# ISPnub_v1_2.net
KiCad netlist of a schematic drawn in EAGLE
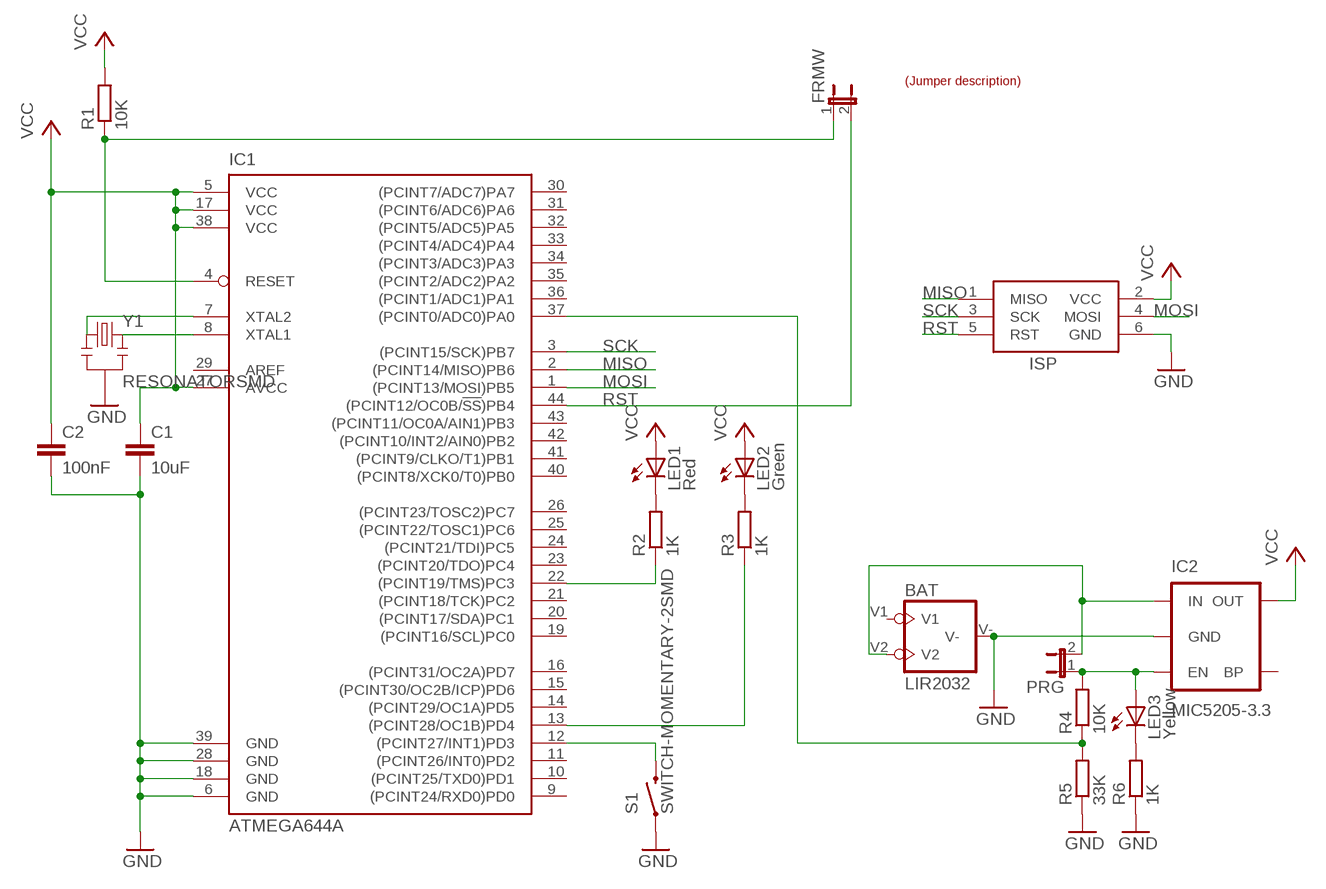
[diagram p0: schematic, sheet 1]

(export (version "E")
  (design (tool "Eeschema 10.0.6"))
  (components
    (comp (ref "BAT")
      (value "LIR2032")
      (footprint "eagle-import:BATT2032")
      (libsource (lib "eagle-import") (part "BATTERY_2032"))
    )
    (comp (ref "C1")
      (value "10uF")
      (footprint "eagle-import:C0805")
      (libsource (lib "eagle-import") (part "C-EUC0805"))
    )
    (comp (ref "C2")
      (value "100nF")
      (footprint "eagle-import:C0805")
      (libsource (lib "eagle-import") (part "C-EUC0805"))
    )
    (comp (ref "FRMW")
      (value "JP1E")
      (footprint "eagle-import:JP1")
      (libsource (lib "eagle-import") (part "JP1E"))
    )
    (comp (ref "IC1")
      (value "ATMEGA644A")
      (footprint "eagle-import:TQFP44")
      (fields (field (name "MPN") "ATMEGA644PV-10AU") (field (name "MPN_1") "ATMEGA1284PV-10AU"))
      (libsource (lib "eagle-import") (part "ATMEGA644A"))
    )
    (comp (ref "IC2")
      (value "MIC5205-3.3")
      (footprint "eagle-import:SOT23-5")
      (libsource (lib "eagle-import") (part "V_REG_LDOSMD"))
    )
    (comp (ref "ISP")
      (value "AVRISP-6")
      (footprint "eagle-import:AVRISP")
      (libsource (lib "eagle-import") (part "AVRISP-6"))
    )
    (comp (ref "LED1")
      (value "Red")
      (footprint "eagle-import:CHIP-LED0805")
      (libsource (lib "eagle-import") (part "LEDCHIP-LED0805"))
    )
    (comp (ref "LED2")
      (value "Green")
      (footprint "eagle-import:CHIP-LED0805")
      (libsource (lib "eagle-import") (part "LEDCHIP-LED0805"))
    )
    (comp (ref "LED3")
      (value "Yellow")
      (footprint "eagle-import:CHIP-LED0805")
      (libsource (lib "eagle-import") (part "LEDCHIP-LED0805"))
    )
    (comp (ref "PRG")
      (value "JP1E")
      (footprint "eagle-import:JP1")
      (libsource (lib "eagle-import") (part "JP1E"))
    )
    (comp (ref "R1")
      (value "10K")
      (footprint "eagle-import:R0805")
      (libsource (lib "eagle-import") (part "R-EU_R0805"))
    )
    (comp (ref "R2")
      (value "1K")
      (footprint "eagle-import:R0805")
      (libsource (lib "eagle-import") (part "R-EU_R0805"))
    )
    (comp (ref "R3")
      (value "1K")
      (footprint "eagle-import:R0805")
      (libsource (lib "eagle-import") (part "R-EU_R0805"))
    )
    (comp (ref "R4")
      (value "10K")
      (footprint "eagle-import:R0402")
      (libsource (lib "eagle-import") (part "R-EU_R0402"))
    )
    (comp (ref "R5")
      (value "33K")
      (footprint "eagle-import:R0402")
      (libsource (lib "eagle-import") (part "R-EU_R0402"))
    )
    (comp (ref "R6")
      (value "1K")
      (footprint "eagle-import:R0805")
      (libsource (lib "eagle-import") (part "R-EU_R0805"))
    )
    (comp (ref "S1")
      (value "SWITCH-MOMENTARY-2SMD")
      (footprint "eagle-import:TACTILE_SWITCH_SMD")
      (libsource (lib "eagle-import") (part "SWITCH-MOMENTARY-2SMD"))
    )
    (comp (ref "U$1")
      (value "LABEL_JUMPER_1X2")
      (footprint "eagle-import:JUMP2_DESC")
      (fields (field (name "OFF") "Normal") (field (name "ON") "Update Firmware"))
      (libsource (lib "eagle-import") (part "LABEL_JUMPER_1X2"))
    )
    (comp (ref "Y1")
      (value "RESONATORSMD")
      (footprint "eagle-import:RESONATOR-SMD")
      (libsource (lib "eagle-import") (part "RESONATORSMD"))
    )
  )
  (nets
    (net (code "1") (name "/MISO") (class "Default")
      (node (ref "IC1") (pin "2") (pinfunction "(PCINT14/MISO)PB6_2") (pintype "bidirectional"))
      (node (ref "ISP") (pin "1") (pinfunction "MISO_1") (pintype "input"))
    )
    (net (code "2") (name "/MOSI") (class "Default")
      (node (ref "IC1") (pin "1") (pinfunction "(PCINT13/MOSI)PB5_1") (pintype "bidirectional"))
      (node (ref "ISP") (pin "4") (pinfunction "MOSI_4") (pintype "output"))
    )
    (net (code "3") (name "/RST") (class "Default")
      (node (ref "FRMW") (pin "2") (pinfunction "2_2") (pintype "passive"))
      (node (ref "IC1") (pin "44") (pinfunction "(PCINT12/OC0B/~{SS})PB4_44") (pintype "bidirectional"))
      (node (ref "ISP") (pin "5") (pinfunction "RST_5") (pintype "output"))
    )
    (net (code "4") (name "/SCK") (class "Default")
      (node (ref "IC1") (pin "3") (pinfunction "(PCINT15/SCK)PB7_3") (pintype "bidirectional"))
      (node (ref "ISP") (pin "3") (pinfunction "SCK_3") (pintype "output"))
    )
    (net (code "5") (name "/V1") (class "Default")
      (node (ref "BAT") (pin "V1") (pinfunction "V1_V1") (pintype "power_in"))
    )
    (net (code "6") (name "GND") (class "Default")
      (node (ref "BAT") (pin "V-") (pinfunction "V-_V-") (pintype "power_in"))
      (node (ref "C1") (pin "2") (pinfunction "2_2") (pintype "passive"))
      (node (ref "C2") (pin "2") (pinfunction "2_2") (pintype "passive"))
      (node (ref "IC1") (pin "18") (pinfunction "GND_18") (pintype "power_in"))
      (node (ref "IC1") (pin "28") (pinfunction "GND_28") (pintype "power_in"))
      (node (ref "IC1") (pin "39") (pinfunction "GND_39") (pintype "power_in"))
      (node (ref "IC1") (pin "6") (pinfunction "GND_6") (pintype "power_in"))
      (node (ref "IC2") (pin "2") (pinfunction "GND_2") (pintype "input"))
      (node (ref "ISP") (pin "6") (pinfunction "GND_6") (pintype "power_in"))
      (node (ref "R5") (pin "1") (pinfunction "1_1") (pintype "passive"))
      (node (ref "R6") (pin "1") (pinfunction "1_1") (pintype "passive"))
      (node (ref "S1") (pin "1") (pinfunction "1_1") (pintype "passive"))
      (node (ref "Y1") (pin "2") (pinfunction "2_2") (pintype "passive"))
    )
    (net (code "7") (name "Net-(IC1-(PCINT0{slash}ADC0)PA0)") (class "Default")
      (node (ref "IC1") (pin "37") (pinfunction "(PCINT0/ADC0)PA0_37") (pintype "bidirectional"))
      (node (ref "R4") (pin "1") (pinfunction "1_1") (pintype "passive"))
      (node (ref "R5") (pin "2") (pinfunction "2_2") (pintype "passive"))
    )
    (net (code "8") (name "Net-(IC1-(PCINT19{slash}TMS)PC3)") (class "Default")
      (node (ref "IC1") (pin "22") (pinfunction "(PCINT19/TMS)PC3_22") (pintype "output"))
      (node (ref "R2") (pin "1") (pinfunction "1_1") (pintype "passive"))
    )
    (net (code "9") (name "Net-(IC1-(PCINT27{slash}INT1)PD3)") (class "Default")
      (node (ref "IC1") (pin "12") (pinfunction "(PCINT27/INT1)PD3_12") (pintype "bidirectional"))
      (node (ref "S1") (pin "3") (pinfunction "2_3") (pintype "passive"))
    )
    (net (code "10") (name "Net-(IC1-(PCINT28{slash}OC1B)PD4)") (class "Default")
      (node (ref "IC1") (pin "13") (pinfunction "(PCINT28/OC1B)PD4_13") (pintype "bidirectional"))
      (node (ref "R3") (pin "1") (pinfunction "1_1") (pintype "passive"))
    )
    (net (code "11") (name "Net-(IC1-RESET)") (class "Default")
      (node (ref "FRMW") (pin "1") (pinfunction "1_1") (pintype "passive"))
      (node (ref "IC1") (pin "4") (pinfunction "RESET_4") (pintype "input"))
      (node (ref "R1") (pin "1") (pinfunction "1_1") (pintype "passive"))
    )
    (net (code "12") (name "Net-(IC1-XTAL1)") (class "Default")
      (node (ref "IC1") (pin "8") (pinfunction "XTAL1_8") (pintype "bidirectional"))
      (node (ref "Y1") (pin "3") (pinfunction "3_3") (pintype "passive"))
    )
    (net (code "13") (name "Net-(IC1-XTAL2)") (class "Default")
      (node (ref "IC1") (pin "7") (pinfunction "XTAL2_7") (pintype "bidirectional"))
      (node (ref "Y1") (pin "1") (pinfunction "1_1") (pintype "passive"))
    )
    (net (code "14") (name "Net-(IC2-EN)") (class "Default")
      (node (ref "IC2") (pin "3") (pinfunction "EN_3") (pintype "input"))
      (node (ref "LED3") (pin "A") (pinfunction "A_A") (pintype "passive"))
      (node (ref "PRG") (pin "1") (pinfunction "1_1") (pintype "passive"))
      (node (ref "R4") (pin "2") (pinfunction "2_2") (pintype "passive"))
    )
    (net (code "15") (name "Net-(IC2-IN)") (class "Default")
      (node (ref "BAT") (pin "V2") (pinfunction "V2_V2") (pintype "power_in"))
      (node (ref "IC2") (pin "1") (pinfunction "IN_1") (pintype "input"))
      (node (ref "PRG") (pin "2") (pinfunction "2_2") (pintype "passive"))
    )
    (net (code "16") (name "Net-(LED1-PadC)") (class "Default")
      (node (ref "LED1") (pin "C") (pinfunction "C_C") (pintype "passive"))
      (node (ref "R2") (pin "2") (pinfunction "2_2") (pintype "passive"))
    )
    (net (code "17") (name "Net-(LED2-PadC)") (class "Default")
      (node (ref "LED2") (pin "C") (pinfunction "C_C") (pintype "passive"))
      (node (ref "R3") (pin "2") (pinfunction "2_2") (pintype "passive"))
    )
    (net (code "18") (name "Net-(LED3-PadC)") (class "Default")
      (node (ref "LED3") (pin "C") (pinfunction "C_C") (pintype "passive"))
      (node (ref "R6") (pin "2") (pinfunction "2_2") (pintype "passive"))
    )
    (net (code "19") (name "VCC") (class "Default")
      (node (ref "C1") (pin "1") (pinfunction "1_1") (pintype "passive"))
      (node (ref "C2") (pin "1") (pinfunction "1_1") (pintype "passive"))
      (node (ref "IC1") (pin "17") (pinfunction "VCC_17") (pintype "power_in"))
      (node (ref "IC1") (pin "27") (pinfunction "AVCC_27") (pintype "power_in"))
      (node (ref "IC1") (pin "38") (pinfunction "VCC_38") (pintype "power_in"))
      (node (ref "IC1") (pin "5") (pinfunction "VCC_5") (pintype "power_in"))
      (node (ref "IC2") (pin "5") (pinfunction "OUT_5") (pintype "passive"))
      (node (ref "ISP") (pin "2") (pinfunction "VCC_2") (pintype "power_in"))
      (node (ref "LED1") (pin "A") (pinfunction "A_A") (pintype "passive"))
      (node (ref "LED2") (pin "A") (pinfunction "A_A") (pintype "passive"))
      (node (ref "R1") (pin "2") (pinfunction "2_2") (pintype "passive"))
    )
    (net (code "20") (name "unconnected-(IC1-(PCINT1{slash}ADC1)PA1-Pad36)") (class "Default")
      (node (ref "IC1") (pin "36") (pinfunction "(PCINT1/ADC1)PA1_36") (pintype "bidirectional"))
    )
    (net (code "21") (name "unconnected-(IC1-(PCINT2{slash}ADC2)PA2-Pad35)") (class "Default")
      (node (ref "IC1") (pin "35") (pinfunction "(PCINT2/ADC2)PA2_35") (pintype "bidirectional"))
    )
    (net (code "22") (name "unconnected-(IC1-(PCINT3{slash}ADC3)PA3-Pad34)") (class "Default")
      (node (ref "IC1") (pin "34") (pinfunction "(PCINT3/ADC3)PA3_34") (pintype "bidirectional"))
    )
    (net (code "23") (name "unconnected-(IC1-(PCINT4{slash}ADC4)PA4-Pad33)") (class "Default")
      (node (ref "IC1") (pin "33") (pinfunction "(PCINT4/ADC4)PA4_33") (pintype "bidirectional"))
    )
    (net (code "24") (name "unconnected-(IC1-(PCINT5{slash}ADC5)PA5-Pad32)") (class "Default")
      (node (ref "IC1") (pin "32") (pinfunction "(PCINT5/ADC5)PA5_32") (pintype "bidirectional"))
    )
    (net (code "25") (name "unconnected-(IC1-(PCINT6{slash}ADC6)PA6-Pad31)") (class "Default")
      (node (ref "IC1") (pin "31") (pinfunction "(PCINT6/ADC6)PA6_31") (pintype "bidirectional"))
    )
    (net (code "26") (name "unconnected-(IC1-(PCINT7{slash}ADC7)PA7-Pad30)") (class "Default")
      (node (ref "IC1") (pin "30") (pinfunction "(PCINT7/ADC7)PA7_30") (pintype "bidirectional"))
    )
    (net (code "27") (name "unconnected-(IC1-(PCINT8{slash}XCK0{slash}T0)PB0-Pad40)") (class "Default")
      (node (ref "IC1") (pin "40") (pinfunction "(PCINT8/XCK0/T0)PB0_40") (pintype "bidirectional"))
    )
    (net (code "28") (name "unconnected-(IC1-(PCINT9{slash}CLKO{slash}T1)PB1-Pad41)") (class "Default")
      (node (ref "IC1") (pin "41") (pinfunction "(PCINT9/CLKO/T1)PB1_41") (pintype "bidirectional"))
    )
    (net (code "29") (name "unconnected-(IC1-(PCINT10{slash}INT2{slash}AIN0)PB2-Pad42)") (class "Default")
      (node (ref "IC1") (pin "42") (pinfunction "(PCINT10/INT2/AIN0)PB2_42") (pintype "bidirectional"))
    )
    (net (code "30") (name "unconnected-(IC1-(PCINT11{slash}OC0A{slash}AIN1)PB3-Pad43)") (class "Default")
      (node (ref "IC1") (pin "43") (pinfunction "(PCINT11/OC0A/AIN1)PB3_43") (pintype "bidirectional"))
    )
    (net (code "31") (name "unconnected-(IC1-(PCINT16{slash}SCL)PC0-Pad19)") (class "Default")
      (node (ref "IC1") (pin "19") (pinfunction "(PCINT16/SCL)PC0_19") (pintype "output"))
    )
    (net (code "32") (name "unconnected-(IC1-(PCINT17{slash}SDA)PC1-Pad20)") (class "Default")
      (node (ref "IC1") (pin "20") (pinfunction "(PCINT17/SDA)PC1_20") (pintype "output"))
    )
    (net (code "33") (name "unconnected-(IC1-(PCINT18{slash}TCK)PC2-Pad21)") (class "Default")
      (node (ref "IC1") (pin "21") (pinfunction "(PCINT18/TCK)PC2_21") (pintype "output"))
    )
    (net (code "34") (name "unconnected-(IC1-(PCINT20{slash}TDO)PC4-Pad23)") (class "Default")
      (node (ref "IC1") (pin "23") (pinfunction "(PCINT20/TDO)PC4_23") (pintype "output"))
    )
    (net (code "35") (name "unconnected-(IC1-(PCINT21{slash}TDI)PC5-Pad24)") (class "Default")
      (node (ref "IC1") (pin "24") (pinfunction "(PCINT21/TDI)PC5_24") (pintype "output"))
    )
    (net (code "36") (name "unconnected-(IC1-(PCINT22{slash}TOSC1)PC6-Pad25)") (class "Default")
      (node (ref "IC1") (pin "25") (pinfunction "(PCINT22/TOSC1)PC6_25") (pintype "output"))
    )
    (net (code "37") (name "unconnected-(IC1-(PCINT23{slash}TOSC2)PC7-Pad26)") (class "Default")
      (node (ref "IC1") (pin "26") (pinfunction "(PCINT23/TOSC2)PC7_26") (pintype "output"))
    )
    (net (code "38") (name "unconnected-(IC1-(PCINT24{slash}RXD0)PD0-Pad9)") (class "Default")
      (node (ref "IC1") (pin "9") (pinfunction "(PCINT24/RXD0)PD0_9") (pintype "bidirectional"))
    )
    (net (code "39") (name "unconnected-(IC1-(PCINT25{slash}TXD0)PD1-Pad10)") (class "Default")
      (node (ref "IC1") (pin "10") (pinfunction "(PCINT25/TXD0)PD1_10") (pintype "bidirectional"))
    )
    (net (code "40") (name "unconnected-(IC1-(PCINT26{slash}INT0)PD2-Pad11)") (class "Default")
      (node (ref "IC1") (pin "11") (pinfunction "(PCINT26/INT0)PD2_11") (pintype "bidirectional"))
    )
    (net (code "41") (name "unconnected-(IC1-(PCINT29{slash}OC1A)PD5-Pad14)") (class "Default")
      (node (ref "IC1") (pin "14") (pinfunction "(PCINT29/OC1A)PD5_14") (pintype "bidirectional"))
    )
    (net (code "42") (name "unconnected-(IC1-(PCINT30{slash}OC2B{slash}ICP)PD6-Pad15)") (class "Default")
      (node (ref "IC1") (pin "15") (pinfunction "(PCINT30/OC2B/ICP)PD6_15") (pintype "bidirectional"))
    )
    (net (code "43") (name "unconnected-(IC1-(PCINT31{slash}OC2A)PD7-Pad16)") (class "Default")
      (node (ref "IC1") (pin "16") (pinfunction "(PCINT31/OC2A)PD7_16") (pintype "bidirectional"))
    )
    (net (code "44") (name "unconnected-(IC1-AREF-Pad29)") (class "Default")
      (node (ref "IC1") (pin "29") (pinfunction "AREF_29") (pintype "passive"))
    )
    (net (code "45") (name "unconnected-(IC2-BP-Pad4)") (class "Default")
      (node (ref "IC2") (pin "4") (pinfunction "BP_4") (pintype "input"))
    )
  )
)
